# Sensor_ExpandBoard_Connection.net
KiCad netlist of a schematic drawn in Altium Designer
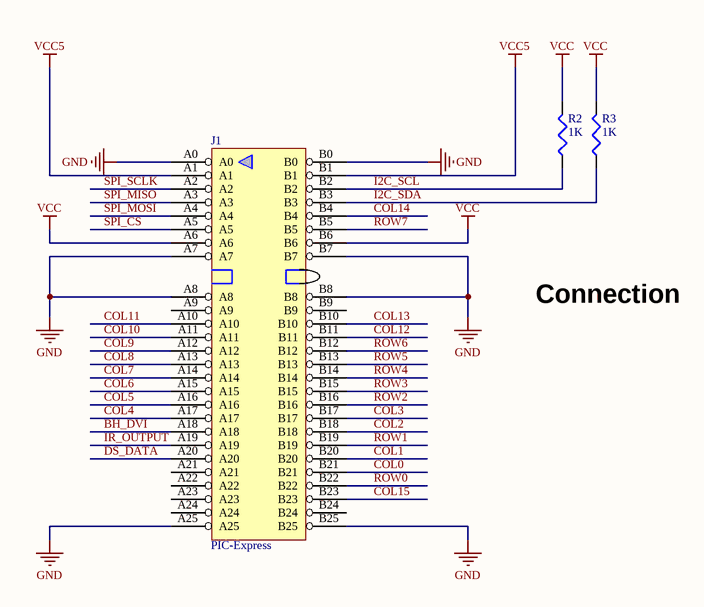
[diagram p0: Sensor_ExpandBoard_Connection.SchDoc]

(export (version "E")
  (design (tool "Eeschema 10.0.6"))
  (components
    (comp (ref "J1") (value "PIC-Express") (footprint "PICE-M") (libsource (lib "step") (part "PIC-Express")))
    (comp (ref "R2")
      (value "1K")
      (footprint "R0603")
      (description "Resistor")
      (fields (field (name "PUBLISHER") "Altium Limited"))
      (libsource (lib "step") (part "Res"))
    )
    (comp (ref "R3")
      (value "1K")
      (footprint "R0603")
      (description "Resistor")
      (fields (field (name "PUBLISHER") "Altium Limited"))
      (libsource (lib "step") (part "Res"))
    )
  )
  (nets
    (net (code "1") (name "/BH_DVI") (class "Default")
      (node (ref "J1") (pin "A18") (pinfunction "A18_A18") (pintype "passive"))
    )
    (net (code "2") (name "/COL0") (class "Default")
      (node (ref "J1") (pin "B21") (pinfunction "B21_B21") (pintype "passive"))
    )
    (net (code "3") (name "/COL1") (class "Default")
      (node (ref "J1") (pin "B20") (pinfunction "B20_B20") (pintype "passive"))
    )
    (net (code "4") (name "/COL2") (class "Default")
      (node (ref "J1") (pin "B18") (pinfunction "B18_B18") (pintype "passive"))
    )
    (net (code "5") (name "/COL3") (class "Default")
      (node (ref "J1") (pin "B17") (pinfunction "B17_B17") (pintype "passive"))
    )
    (net (code "6") (name "/COL4") (class "Default")
      (node (ref "J1") (pin "A17") (pinfunction "A17_A17") (pintype "passive"))
    )
    (net (code "7") (name "/COL5") (class "Default")
      (node (ref "J1") (pin "A16") (pinfunction "A16_A16") (pintype "passive"))
    )
    (net (code "8") (name "/COL6") (class "Default")
      (node (ref "J1") (pin "A15") (pinfunction "A15_A15") (pintype "passive"))
    )
    (net (code "9") (name "/COL7") (class "Default")
      (node (ref "J1") (pin "A14") (pinfunction "A14_A14") (pintype "passive"))
    )
    (net (code "10") (name "/COL8") (class "Default")
      (node (ref "J1") (pin "A13") (pinfunction "A13_A13") (pintype "passive"))
    )
    (net (code "11") (name "/COL9") (class "Default")
      (node (ref "J1") (pin "A12") (pinfunction "A12_A12") (pintype "passive"))
    )
    (net (code "12") (name "/COL10") (class "Default")
      (node (ref "J1") (pin "A11") (pinfunction "A11_A11") (pintype "passive"))
    )
    (net (code "13") (name "/COL11") (class "Default")
      (node (ref "J1") (pin "A10") (pinfunction "A10_A10") (pintype "passive"))
    )
    (net (code "14") (name "/COL12") (class "Default")
      (node (ref "J1") (pin "B11") (pinfunction "B11_B11") (pintype "passive"))
    )
    (net (code "15") (name "/COL13") (class "Default")
      (node (ref "J1") (pin "B10") (pinfunction "B10_B10") (pintype "passive"))
    )
    (net (code "16") (name "/COL14") (class "Default")
      (node (ref "J1") (pin "B4") (pinfunction "B4_B4") (pintype "passive"))
    )
    (net (code "17") (name "/COL15") (class "Default")
      (node (ref "J1") (pin "B23") (pinfunction "B23_B23") (pintype "passive"))
    )
    (net (code "18") (name "/DS_DATA") (class "Default")
      (node (ref "J1") (pin "A20") (pinfunction "A20_A20") (pintype "passive"))
    )
    (net (code "19") (name "/I2C_SCL") (class "Default")
      (node (ref "J1") (pin "B2") (pinfunction "B2_B2") (pintype "passive"))
      (node (ref "R2") (pin "1") (pinfunction "1_1") (pintype "passive"))
    )
    (net (code "20") (name "/I2C_SDA") (class "Default")
      (node (ref "J1") (pin "B3") (pinfunction "B3_B3") (pintype "passive"))
      (node (ref "R3") (pin "1") (pinfunction "1_1") (pintype "passive"))
    )
    (net (code "21") (name "/IR_OUTPUT") (class "Default")
      (node (ref "J1") (pin "A19") (pinfunction "A19_A19") (pintype "passive"))
    )
    (net (code "22") (name "/ROW0") (class "Default")
      (node (ref "J1") (pin "B22") (pinfunction "B22_B22") (pintype "passive"))
    )
    (net (code "23") (name "/ROW1") (class "Default")
      (node (ref "J1") (pin "B19") (pinfunction "B19_B19") (pintype "passive"))
    )
    (net (code "24") (name "/ROW2") (class "Default")
      (node (ref "J1") (pin "B16") (pinfunction "B16_B16") (pintype "passive"))
    )
    (net (code "25") (name "/ROW3") (class "Default")
      (node (ref "J1") (pin "B15") (pinfunction "B15_B15") (pintype "passive"))
    )
    (net (code "26") (name "/ROW4") (class "Default")
      (node (ref "J1") (pin "B14") (pinfunction "B14_B14") (pintype "passive"))
    )
    (net (code "27") (name "/ROW5") (class "Default")
      (node (ref "J1") (pin "B13") (pinfunction "B13_B13") (pintype "passive"))
    )
    (net (code "28") (name "/ROW6") (class "Default")
      (node (ref "J1") (pin "B12") (pinfunction "B12_B12") (pintype "passive"))
    )
    (net (code "29") (name "/ROW7") (class "Default")
      (node (ref "J1") (pin "B5") (pinfunction "B5_B5") (pintype "passive"))
    )
    (net (code "30") (name "/SPI_MISO") (class "Default")
      (node (ref "J1") (pin "A3") (pinfunction "A3_A3") (pintype "passive"))
    )
    (net (code "31") (name "/SPI_MOSI") (class "Default")
      (node (ref "J1") (pin "A4") (pinfunction "A4_A4") (pintype "passive"))
    )
    (net (code "32") (name "/SPI_SCLK") (class "Default")
      (node (ref "J1") (pin "A2") (pinfunction "A2_A2") (pintype "passive"))
    )
    (net (code "33") (name "/SPI_~{CS}") (class "Default")
      (node (ref "J1") (pin "A5") (pinfunction "A5_A5") (pintype "passive"))
    )
    (net (code "34") (name "GND") (class "Default")
      (node (ref "J1") (pin "A0") (pinfunction "A0_A0") (pintype "passive"))
      (node (ref "J1") (pin "A25") (pinfunction "A25_A25") (pintype "passive"))
      (node (ref "J1") (pin "A7") (pinfunction "A7_A7") (pintype "passive"))
      (node (ref "J1") (pin "A8") (pinfunction "A8_A8") (pintype "passive"))
      (node (ref "J1") (pin "B0") (pinfunction "B0_B0") (pintype "passive"))
      (node (ref "J1") (pin "B25") (pinfunction "B25_B25") (pintype "passive"))
      (node (ref "J1") (pin "B7") (pinfunction "B7_B7") (pintype "passive"))
      (node (ref "J1") (pin "B8") (pinfunction "B8_B8") (pintype "passive"))
    )
    (net (code "35") (name "VCC") (class "Default")
      (node (ref "J1") (pin "A6") (pinfunction "A6_A6") (pintype "passive"))
      (node (ref "J1") (pin "B6") (pinfunction "B6_B6") (pintype "passive"))
      (node (ref "R2") (pin "2") (pinfunction "2_2") (pintype "passive"))
      (node (ref "R3") (pin "2") (pinfunction "2_2") (pintype "passive"))
    )
    (net (code "36") (name "VCC5") (class "Default")
      (node (ref "J1") (pin "A1") (pinfunction "A1_A1") (pintype "passive"))
      (node (ref "J1") (pin "B1") (pinfunction "B1_B1") (pintype "passive"))
    )
    (net (code "37") (name "unconnected-(J1-PadA9)") (class "Default")
      (node (ref "J1") (pin "A9") (pinfunction "A9_A9") (pintype "passive"))
    )
    (net (code "38") (name "unconnected-(J1-PadA21)") (class "Default")
      (node (ref "J1") (pin "A21") (pinfunction "A21_A21") (pintype "passive"))
    )
    (net (code "39") (name "unconnected-(J1-PadA22)") (class "Default")
      (node (ref "J1") (pin "A22") (pinfunction "A22_A22") (pintype "passive"))
    )
    (net (code "40") (name "unconnected-(J1-PadA23)") (class "Default")
      (node (ref "J1") (pin "A23") (pinfunction "A23_A23") (pintype "passive"))
    )
    (net (code "41") (name "unconnected-(J1-PadA24)") (class "Default")
      (node (ref "J1") (pin "A24") (pinfunction "A24_A24") (pintype "passive"))
    )
    (net (code "42") (name "unconnected-(J1-PadB9)") (class "Default")
      (node (ref "J1") (pin "B9") (pinfunction "B9_B9") (pintype "passive"))
    )
    (net (code "43") (name "unconnected-(J1-PadB24)") (class "Default")
      (node (ref "J1") (pin "B24") (pinfunction "B24_B24") (pintype "passive"))
    )
  )
)
